# GPS_Peggy_Tracker.net
KiCad netlist of a schematic drawn in Altium Designer
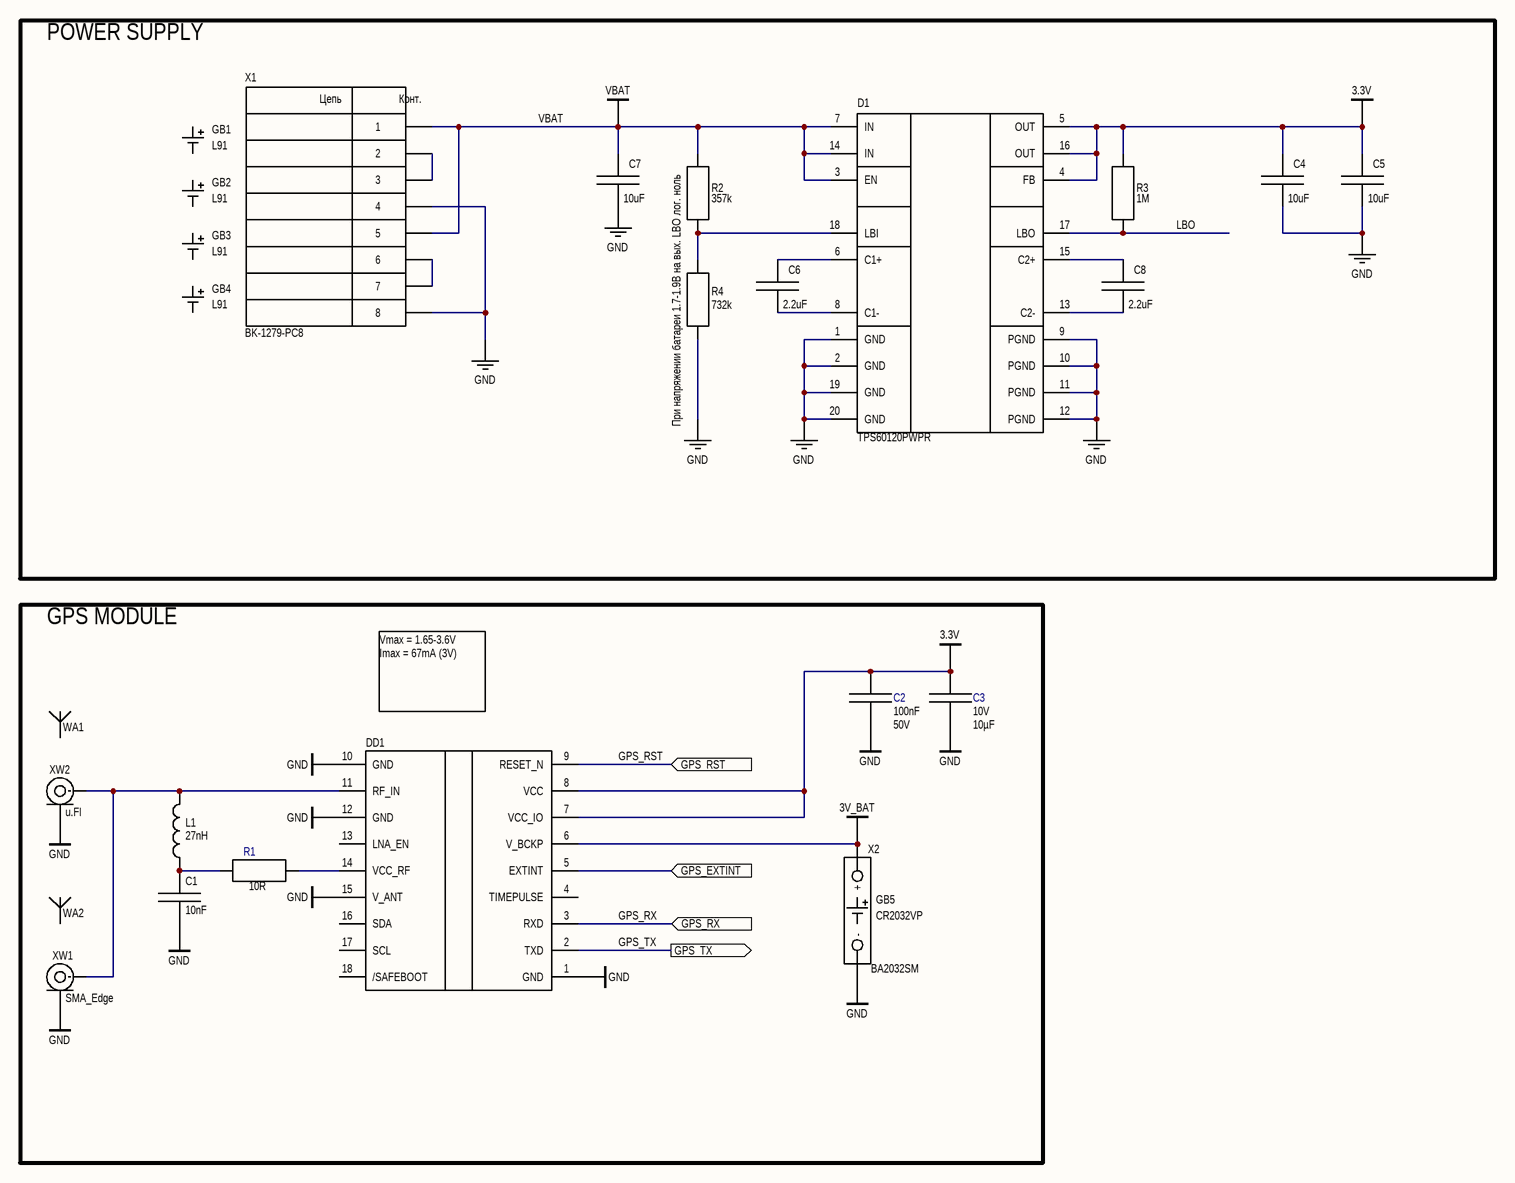
[diagram p0: Схема питания и GPS Peggy Tracker.SchDoc]

(export (version "E")
  (design (tool "Eeschema 10.0.6"))
  (components
    (comp (ref "C1")
      (value "10nF")
      (footprint "standard:CH0603C")
      (description "CAP CER 10000PF 50V X7R 0603")
      (fields (field (name "MANUFACTURER") "Murata Electronics"))
      (libsource (lib "Discrete") (part "Capacitor"))
    )
    (comp (ref "C2")
      (value "100nF")
      (footprint "CAPC1608X09N")
      (description "CAP CER 0.1UF 50V X7R 0603")
      (fields
        (field (name "VOLTAGE RATING") "50V")
        (field (name "TOLERANCE") "10%")
        (field (name "MANUFACTURER PART NUMBER") "GCM188R71H104KA57D")
        (field (name "SOURCE") "Meteo_1.SCHLIB")
      )
      (libsource (lib "Sergek Concord Server") (part "CAP-NP-2"))
    )
    (comp (ref "C3")
      (value "CL21Y106KPQVPNE")
      (footprint "CAPC2013X135X45NL10T25")
      (description "CAP CER 10UF 10V X7S 0805")
      (fields
        (field (name "MANUFACTURER") "Samsung")
        (field (name "VOLTAGE RATING") "10V")
        (field (name "CAPACITANCE") "10µF")
        (field (name "TOLERANCE") "10%")
      )
      (libsource (lib "Sergek Concord Server") (part "CAP-NP-2"))
    )
    (comp (ref "C4")
      (value "10uF")
      (footprint "CH1206C")
      (description "Cap Ceramic 10uF 16V X7R 20% SMD 1206 125°C Embossed T/R")
      (fields
        (field (name "MANUFACTURER") "Samsung Electro-Mechanics")
        (field (name "MANUFACTURER PART NUMBER") "CL31B106MOHNNNE")
      )
      (libsource (lib "Schlib") (part "Capacitor"))
    )
    (comp (ref "C5")
      (value "10uF")
      (footprint "CH1206C")
      (description "Cap Ceramic 10uF 16V X7R 20% SMD 1206 125°C Embossed T/R")
      (fields
        (field (name "MANUFACTURER") "Samsung Electro-Mechanics")
        (field (name "MANUFACTURER PART NUMBER") "CL31B106MOHNNNE")
      )
      (libsource (lib "Schlib") (part "Capacitor"))
    )
    (comp (ref "C6")
      (value "2.2uF")
      (footprint "CH0805C")
      (description "Cap Ceramic 10uF 16V X7R 20% SMD 1206 125°C Embossed T/R")
      (fields
        (field (name "MANUFACTURER") "Murata Electronics")
        (field (name "MANUFACTURER PART NUMBER") "CL31B106MOHNNNE")
      )
      (libsource (lib "Schlib") (part "Capacitor"))
    )
    (comp (ref "C7")
      (value "10uF")
      (footprint "CH1206C")
      (description "Cap Ceramic 10uF 16V X7R 20% SMD 1206 125°C Embossed T/R")
      (fields
        (field (name "MANUFACTURER") "Samsung Electro-Mechanics")
        (field (name "MANUFACTURER PART NUMBER") "CL31B106MOHNNNE")
      )
      (libsource (lib "Schlib") (part "Capacitor"))
    )
    (comp (ref "C8")
      (value "2.2uF")
      (footprint "CH0805C")
      (description "Cap Ceramic 10uF 16V X7R 20% SMD 1206 125°C Embossed T/R")
      (fields
        (field (name "MANUFACTURER") "Murata Electronics")
        (field (name "MANUFACTURER PART NUMBER") "CL31B106MOHNNNE")
      )
      (libsource (lib "Schlib") (part "Capacitor"))
    )
    (comp (ref "D1")
      (value "TPS60120PWPR")
      (footprint "20-TSSOP (PAD)")
      (description "Charge Pump Switching Regulator 3.3V")
      (fields (field (name "MANUFACTURER") "Texas Instruments"))
      (libsource (lib "Power Supplies") (part "TPS60120PWPR"))
    )
    (comp (ref "DD1")
      (value "MAX-M8C-0")
      (footprint "MOD: MAX-M8C-0")
      (description "RF RCVR GNSS/GPS 1.575GHZ 18LCC")
      (fields (field (name "MANUFACTURER") "U-Blox"))
      (libsource (lib "Module") (part "MAX-M8C-0"))
    )
    (comp (ref "GB1")
      (value "L91")
      (fields (field (name "MANUFACTURER") "Energizer Battery Company"))
      (libsource (lib "Power Supplies") (part "Battery_1CELL"))
    )
    (comp (ref "GB2")
      (value "L91")
      (fields (field (name "MANUFACTURER") "Energizer Battery Company"))
      (libsource (lib "Power Supplies") (part "Battery_1CELL"))
    )
    (comp (ref "GB3")
      (value "L91")
      (fields (field (name "MANUFACTURER") "Energizer Battery Company"))
      (libsource (lib "Power Supplies") (part "Battery_1CELL"))
    )
    (comp (ref "GB4")
      (value "L91")
      (fields (field (name "MANUFACTURER") "Energizer Battery Company"))
      (libsource (lib "Power Supplies") (part "Battery_1CELL"))
    )
    (comp (ref "GB5")
      (value "CR2032VP")
      (fields (field (name "MANUFACTURER") "Energizer Battery Company"))
      (libsource (lib "Power Supplies") (part "Battery_1CELL"))
    )
    (comp (ref "L1")
      (value "27nH")
      (footprint "standard:CH0603L")
      (fields (field (name "MANUFACTURER") "Murata Electronics"))
      (libsource (lib "Discrete") (part "Inductor"))
    )
    (comp (ref "R1")
      (value "10R")
      (footprint "standard:CH0603R")
      (description "RES 10 OHM 5% 1/3W 0603")
      (fields (field (name "MANUFACTURER") "KOA Speer Electronics, Inc."))
      (libsource (lib "") (part "Resistor_1"))
    )
    (comp (ref "R2")
      (value "357k")
      (footprint "standard:CH0603R")
      (fields (field (name "MANUFACTURER") "YAGEO"))
      (libsource (lib "Discrete") (part "Resistor"))
    )
    (comp (ref "R3")
      (value "1M")
      (footprint "standard:CH0603R")
      (fields (field (name "MANUFACTURER") "YAGEO"))
      (libsource (lib "Discrete") (part "Resistor"))
    )
    (comp (ref "R4")
      (value "732k")
      (footprint "standard:CH0603R")
      (fields (field (name "MANUFACTURER") "YAGEO"))
      (libsource (lib "Discrete") (part "Resistor"))
    )
    (comp (ref "WA1")
      (value "CRJKS0010-LNA-G65U")
      (description "1.583GHz GPS Ceramic Patch RF Antenna 1.559GHz ~ 1.610GHz 17dBi - -")
      (fields (field (name "MANUFACTURER") "NimbeLink, LLC"))
      (libsource (lib "Analog") (part "Antenna 1pin"))
    )
    (comp (ref "WA2")
      (value "MIKE3A/3M/SMAM/S/S/17")
      (description "1.575GHz GPS Module RF Antenna - 28dB SMA Male Adhesive, Magnetic")
      (fields (field (name "MANUFACTURER") "Siretta Ltd"))
      (libsource (lib "Analog") (part "Antenna 1pin"))
    )
    (comp (ref "X1")
      (value "BK-1279-PC8")
      (footprint "custom:CON: BK-1279-PC8")
      (description "BATTERY HOLDER AA 4 CELL PC PIN")
      (fields (field (name "MANUFACTURER") "MPD (Memory Protection Devices)"))
      (libsource (lib "Connectors") (part "8-Connector"))
    )
    (comp (ref "X2")
      (value "BA2032SM")
      (footprint "custom:CON: BA2032SM")
      (fields (field (name "MANUFACTURER") "MPD (Memory Protection Devices)"))
      (libsource (lib "Connectors") (part "Holder_1Cell"))
    )
    (comp (ref "XW1")
      (value "SMA_Edge")
      (footprint "CON: SMA - Edge")
      (description "RF")
      (fields (field (name "MANUFACTURER") "Molex"))
      (libsource (lib "Connectors") (part "SMA"))
    )
    (comp (ref "XW2")
      (value "u.Fl")
      (footprint "custom:CON: u.Fl")
      (description "RF")
      (fields (field (name "MANUFACTURER") "Hirose Electric Co Ltd"))
      (libsource (lib "Connectors") (part "u.Fl"))
    )
  )
  (nets
    (net (code "1") (name "/GPS_EXTINT") (class "Default")
      (node (ref "DD1") (pin "5") (pinfunction "EXTINT_5") (pintype "passive"))
    )
    (net (code "2") (name "/GPS_RST") (class "Default")
      (node (ref "DD1") (pin "9") (pinfunction "RESET_N_9") (pintype "passive"))
    )
    (net (code "3") (name "/GPS_RX") (class "Default")
      (node (ref "DD1") (pin "3") (pinfunction "RXD_3") (pintype "passive"))
    )
    (net (code "4") (name "/GPS_TX") (class "Default")
      (node (ref "DD1") (pin "2") (pinfunction "TXD_2") (pintype "passive"))
    )
    (net (code "5") (name "/LBO") (class "Default")
      (node (ref "D1") (pin "17") (pinfunction "LBO_17") (pintype "power_in"))
      (node (ref "R3") (pin "1") (pinfunction "1_1") (pintype "passive"))
    )
    (net (code "6") (name "3.3V") (class "Default")
      (node (ref "C2") (pin "1") (pinfunction "1_1") (pintype "passive"))
      (node (ref "C3") (pin "2") (pinfunction "2_2") (pintype "passive"))
      (node (ref "C4") (pin "1") (pinfunction "1_1") (pintype "passive"))
      (node (ref "C5") (pin "1") (pinfunction "1_1") (pintype "passive"))
      (node (ref "D1") (pin "16") (pinfunction "OUT_16") (pintype "power_in"))
      (node (ref "D1") (pin "4") (pinfunction "FB_4") (pintype "power_in"))
      (node (ref "D1") (pin "5") (pinfunction "OUT_5") (pintype "power_in"))
      (node (ref "DD1") (pin "7") (pinfunction "VCC_IO_7") (pintype "passive"))
      (node (ref "DD1") (pin "8") (pinfunction "VCC_8") (pintype "passive"))
      (node (ref "R3") (pin "2") (pinfunction "2_2") (pintype "passive"))
    )
    (net (code "7") (name "3V_BAT") (class "Default")
      (node (ref "DD1") (pin "6") (pinfunction "V_BCKP_6") (pintype "passive"))
      (node (ref "X2") (pin "1") (pinfunction "+_1") (pintype "power_in"))
    )
    (net (code "8") (name "GND") (class "Default")
      (node (ref "C1") (pin "2") (pinfunction "2_2") (pintype "passive"))
      (node (ref "C2") (pin "2") (pinfunction "2_2") (pintype "passive"))
      (node (ref "C3") (pin "1") (pinfunction "1_1") (pintype "passive"))
      (node (ref "C4") (pin "2") (pinfunction "2_2") (pintype "passive"))
      (node (ref "C5") (pin "2") (pinfunction "2_2") (pintype "passive"))
      (node (ref "C7") (pin "2") (pinfunction "2_2") (pintype "passive"))
      (node (ref "D1") (pin "1") (pinfunction "GND_1") (pintype "power_in"))
      (node (ref "D1") (pin "10") (pinfunction "PGND_10") (pintype "power_in"))
      (node (ref "D1") (pin "11") (pinfunction "PGND_11") (pintype "power_in"))
      (node (ref "D1") (pin "12") (pinfunction "PGND_12") (pintype "power_in"))
      (node (ref "D1") (pin "19") (pinfunction "GND_19") (pintype "power_in"))
      (node (ref "D1") (pin "2") (pinfunction "GND_2") (pintype "power_in"))
      (node (ref "D1") (pin "20") (pinfunction "GND_20") (pintype "power_in"))
      (node (ref "D1") (pin "9") (pinfunction "PGND_9") (pintype "power_in"))
      (node (ref "DD1") (pin "1") (pinfunction "GND_1") (pintype "passive"))
      (node (ref "DD1") (pin "10") (pinfunction "GND_10") (pintype "passive"))
      (node (ref "DD1") (pin "12") (pinfunction "GND_12") (pintype "passive"))
      (node (ref "DD1") (pin "15") (pinfunction "V_ANT_15") (pintype "passive"))
      (node (ref "R4") (pin "1") (pinfunction "1_1") (pintype "passive"))
      (node (ref "X1") (pin "4") (pinfunction "4_4") (pintype "power_in"))
      (node (ref "X1") (pin "8") (pinfunction "8_8") (pintype "power_in"))
      (node (ref "X2") (pin "2") (pinfunction "-_2") (pintype "power_in"))
      (node (ref "XW1") (pin "2") (pinfunction "IN_2") (pintype "passive"))
      (node (ref "XW2") (pin "2") (pinfunction "IN_2") (pintype "passive"))
    )
    (net (code "9") (name "Net-(C1-Pad1)") (class "Default")
      (node (ref "C1") (pin "1") (pinfunction "1_1") (pintype "passive"))
      (node (ref "L1") (pin "1") (pinfunction "1_1") (pintype "passive"))
      (node (ref "R1") (pin "1") (pinfunction "1_1") (pintype "passive"))
    )
    (net (code "10") (name "Net-(D1-C1+)") (class "Default")
      (node (ref "C6") (pin "1") (pinfunction "1_1") (pintype "passive"))
      (node (ref "D1") (pin "6") (pinfunction "C1+_6") (pintype "power_in"))
    )
    (net (code "11") (name "Net-(D1-C1-)") (class "Default")
      (node (ref "C6") (pin "2") (pinfunction "2_2") (pintype "passive"))
      (node (ref "D1") (pin "8") (pinfunction "C1-_8") (pintype "power_in"))
    )
    (net (code "12") (name "Net-(D1-C2+)") (class "Default")
      (node (ref "C8") (pin "1") (pinfunction "1_1") (pintype "passive"))
      (node (ref "D1") (pin "15") (pinfunction "C2+_15") (pintype "power_in"))
    )
    (net (code "13") (name "Net-(D1-C2-)") (class "Default")
      (node (ref "C8") (pin "2") (pinfunction "2_2") (pintype "passive"))
      (node (ref "D1") (pin "13") (pinfunction "C2-_13") (pintype "power_in"))
    )
    (net (code "14") (name "Net-(D1-LBI)") (class "Default")
      (node (ref "D1") (pin "18") (pinfunction "LBI_18") (pintype "power_in"))
      (node (ref "R2") (pin "1") (pinfunction "1_1") (pintype "passive"))
      (node (ref "R4") (pin "2") (pinfunction "2_2") (pintype "passive"))
    )
    (net (code "15") (name "Net-(DD1-RF_IN)") (class "Default")
      (node (ref "DD1") (pin "11") (pinfunction "RF_IN_11") (pintype "passive"))
      (node (ref "L1") (pin "2") (pinfunction "2_2") (pintype "passive"))
      (node (ref "XW1") (pin "1") (pinfunction "IN_1") (pintype "passive"))
      (node (ref "XW2") (pin "1") (pinfunction "IN_1") (pintype "passive"))
    )
    (net (code "16") (name "Net-(DD1-VCC_RF)") (class "Default")
      (node (ref "DD1") (pin "14") (pinfunction "VCC_RF_14") (pintype "passive"))
      (node (ref "R1") (pin "2") (pinfunction "2_2") (pintype "passive"))
    )
    (net (code "17") (name "Net-(X1-Pad2)") (class "Default")
      (node (ref "X1") (pin "2") (pinfunction "2_2") (pintype "passive"))
      (node (ref "X1") (pin "3") (pinfunction "3_3") (pintype "power_in"))
    )
    (net (code "18") (name "Net-(X1-Pad6)") (class "Default")
      (node (ref "X1") (pin "6") (pinfunction "6_6") (pintype "power_in"))
      (node (ref "X1") (pin "7") (pinfunction "7_7") (pintype "power_in"))
    )
    (net (code "19") (name "VBAT") (class "Default")
      (node (ref "C7") (pin "1") (pinfunction "1_1") (pintype "passive"))
      (node (ref "D1") (pin "14") (pinfunction "IN_14") (pintype "power_in"))
      (node (ref "D1") (pin "3") (pinfunction "EN_3") (pintype "power_in"))
      (node (ref "D1") (pin "7") (pinfunction "IN_7") (pintype "power_in"))
      (node (ref "R2") (pin "2") (pinfunction "2_2") (pintype "passive"))
      (node (ref "X1") (pin "1") (pinfunction "1_1") (pintype "passive"))
      (node (ref "X1") (pin "5") (pinfunction "5_5") (pintype "power_in"))
    )
    (net (code "20") (name "unconnected-(DD1-LNA_EN-Pad13)") (class "Default")
      (node (ref "DD1") (pin "13") (pinfunction "LNA_EN_13") (pintype "passive"))
    )
    (net (code "21") (name "unconnected-(DD1-SCL-Pad17)") (class "Default")
      (node (ref "DD1") (pin "17") (pinfunction "SCL_17") (pintype "passive"))
    )
    (net (code "22") (name "unconnected-(DD1-SDA-Pad16)") (class "Default")
      (node (ref "DD1") (pin "16") (pinfunction "SDA_16") (pintype "passive"))
    )
    (net (code "23") (name "unconnected-(DD1-TIMEPULSE-Pad4)") (class "Default")
      (node (ref "DD1") (pin "4") (pinfunction "TIMEPULSE_4") (pintype "passive"))
    )
    (net (code "24") (name "unconnected-(DD1-{slash}SAFEBOOT-Pad18)") (class "Default")
      (node (ref "DD1") (pin "18") (pinfunction "/SAFEBOOT_18") (pintype "passive"))
    )
    (net (code "25") (name "unconnected-(GB1-+-Pad1)") (class "Default")
      (node (ref "GB1") (pin "1") (pinfunction "+_1") (pintype "passive"))
    )
    (net (code "26") (name "unconnected-(GB1---Pad2)") (class "Default")
      (node (ref "GB1") (pin "2") (pinfunction "-_2") (pintype "passive"))
    )
    (net (code "27") (name "unconnected-(GB2-+-Pad1)") (class "Default")
      (node (ref "GB2") (pin "1") (pinfunction "+_1") (pintype "passive"))
    )
    (net (code "28") (name "unconnected-(GB2---Pad2)") (class "Default")
      (node (ref "GB2") (pin "2") (pinfunction "-_2") (pintype "passive"))
    )
    (net (code "29") (name "unconnected-(GB3-+-Pad1)") (class "Default")
      (node (ref "GB3") (pin "1") (pinfunction "+_1") (pintype "passive"))
    )
    (net (code "30") (name "unconnected-(GB3---Pad2)") (class "Default")
      (node (ref "GB3") (pin "2") (pinfunction "-_2") (pintype "passive"))
    )
    (net (code "31") (name "unconnected-(GB4-+-Pad1)") (class "Default")
      (node (ref "GB4") (pin "1") (pinfunction "+_1") (pintype "passive"))
    )
    (net (code "32") (name "unconnected-(GB4---Pad2)") (class "Default")
      (node (ref "GB4") (pin "2") (pinfunction "-_2") (pintype "passive"))
    )
    (net (code "33") (name "unconnected-(GB5-+-Pad1)") (class "Default")
      (node (ref "GB5") (pin "1") (pinfunction "+_1") (pintype "passive"))
    )
    (net (code "34") (name "unconnected-(GB5---Pad2)") (class "Default")
      (node (ref "GB5") (pin "2") (pinfunction "-_2") (pintype "passive"))
    )
    (net (code "35") (name "unconnected-(WA1-Pad1)") (class "Default")
      (node (ref "WA1") (pin "1") (pinfunction "1_1") (pintype "passive"))
    )
    (net (code "36") (name "unconnected-(WA2-Pad1)") (class "Default")
      (node (ref "WA2") (pin "1") (pinfunction "1_1") (pintype "passive"))
    )
  )
)
